# PIRT1280A1-12-breakout.net
KiCad netlist of a schematic drawn in EAGLE
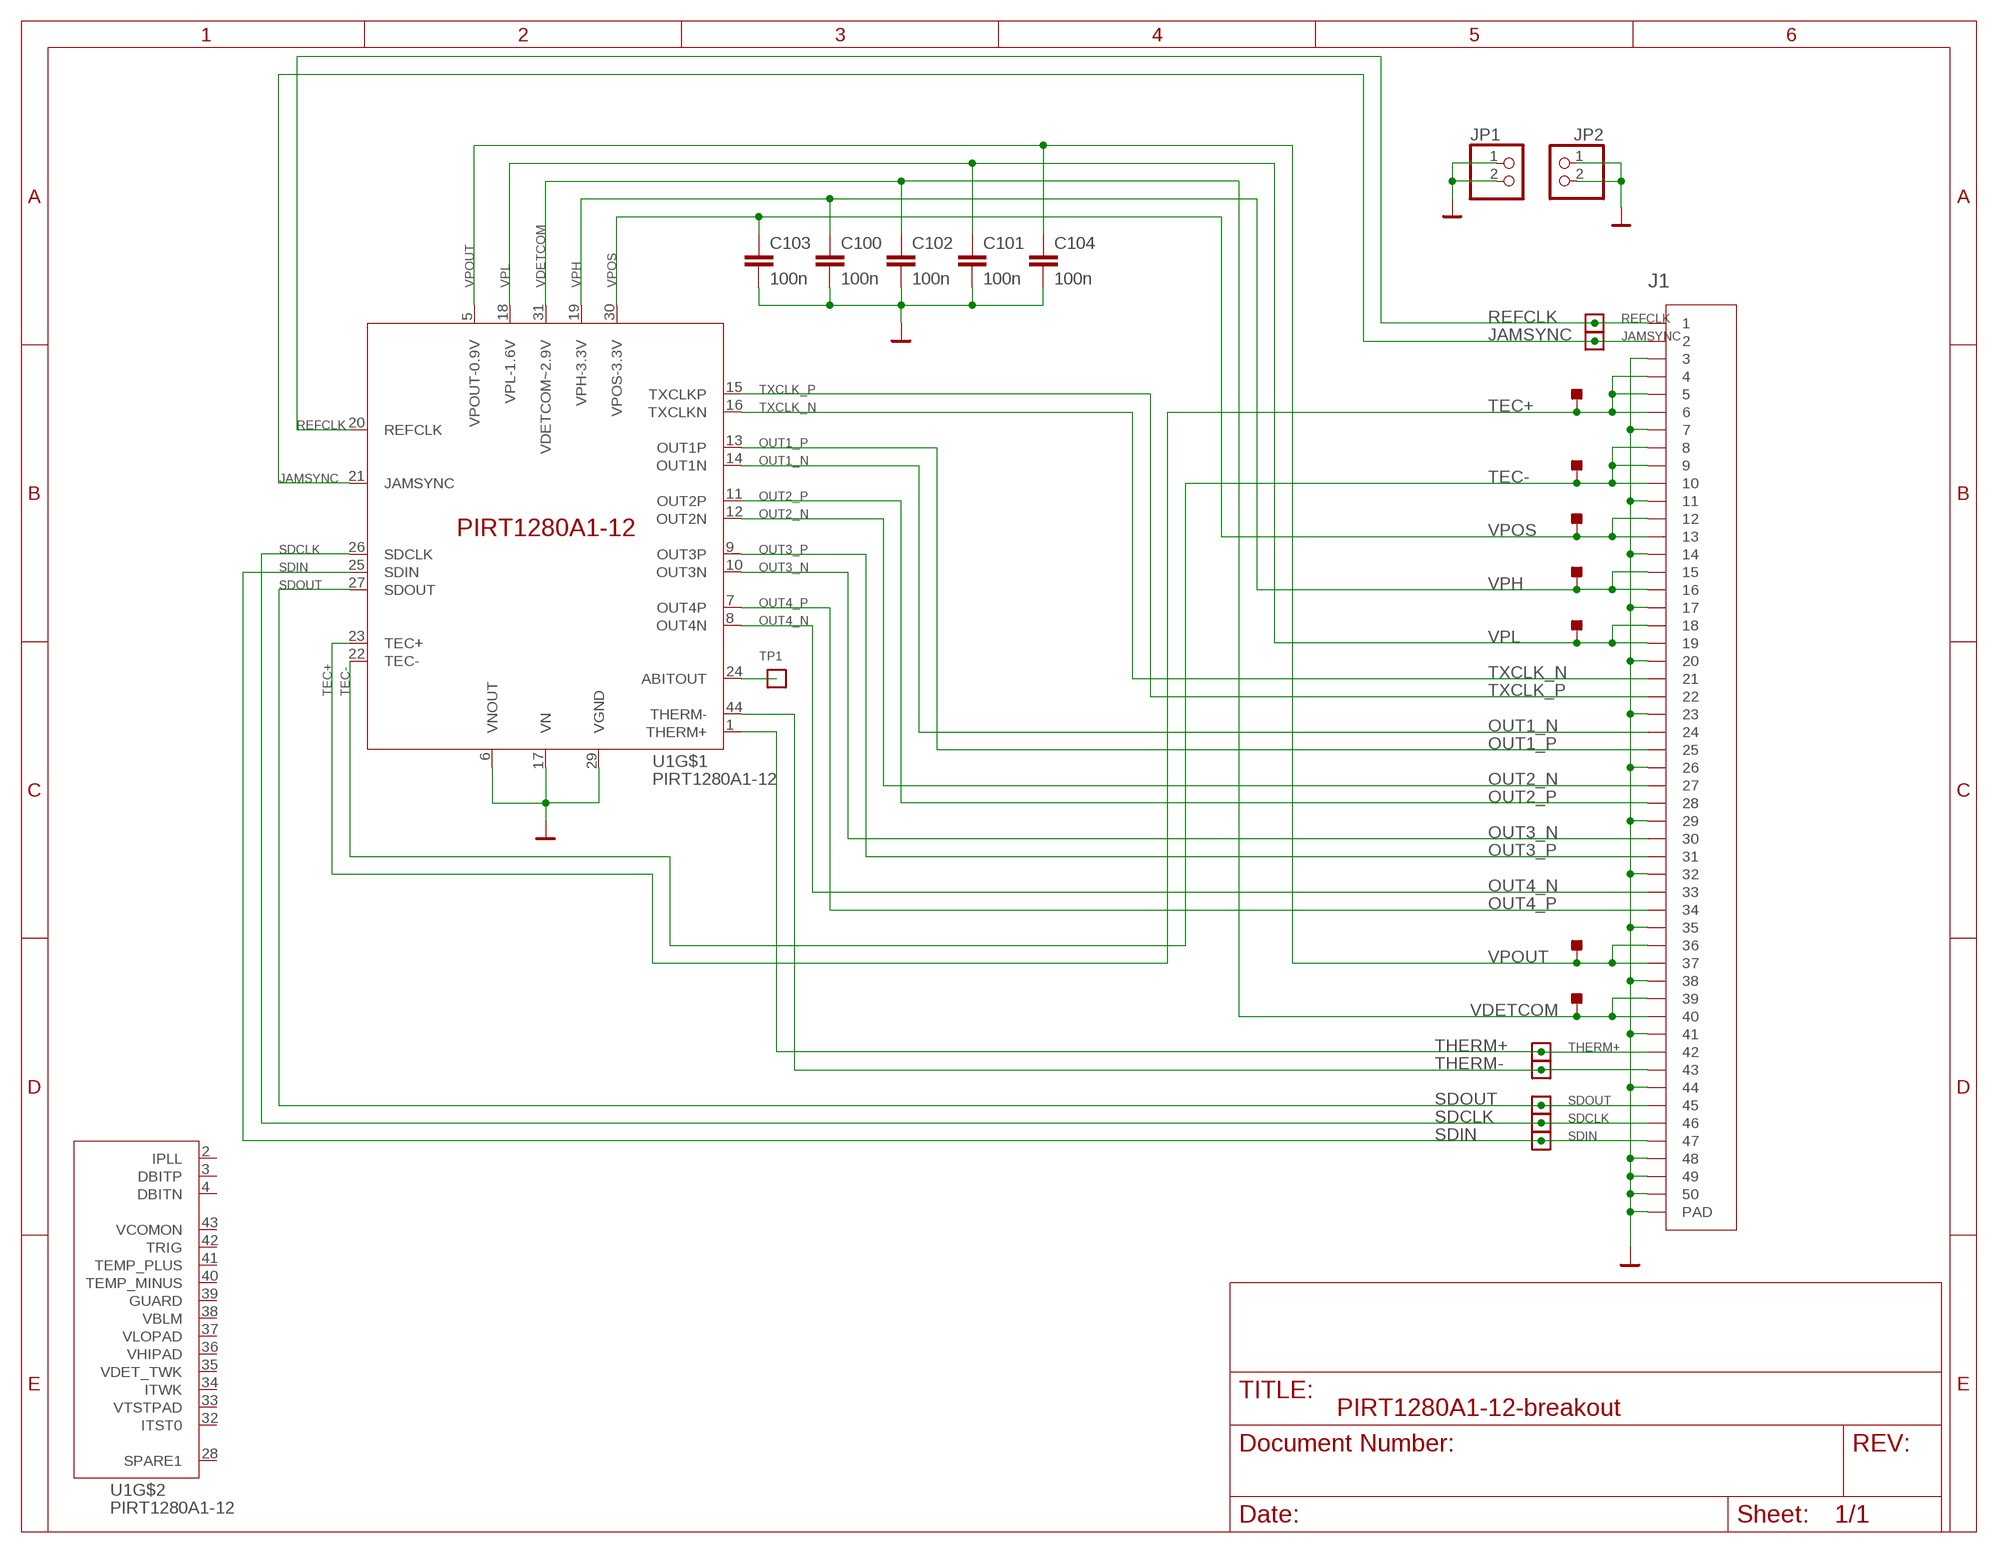
[diagram p0: schematic, sheet 1]

(export (version "E")
  (design (tool "Eeschema 10.0.6"))
  (components
    (comp (ref "C100")
      (value "100n")
      (footprint "eagle-import:.0805-A")
      (libsource (lib "eagle-import") (part "C-EU0805-A"))
    )
    (comp (ref "C101")
      (value "100n")
      (footprint "eagle-import:.0805-A")
      (libsource (lib "eagle-import") (part "C-EU0805-A"))
    )
    (comp (ref "C102")
      (value "100n")
      (footprint "eagle-import:.0805-A")
      (libsource (lib "eagle-import") (part "C-EU0805-A"))
    )
    (comp (ref "C103")
      (value "100n")
      (footprint "eagle-import:.0805-A")
      (libsource (lib "eagle-import") (part "C-EU0805-A"))
    )
    (comp (ref "C104")
      (value "100n")
      (footprint "eagle-import:.0805-A")
      (libsource (lib "eagle-import") (part "C-EU0805-A"))
    )
    (comp (ref "J1")
      (value "5-1734592-0")
      (footprint "eagle-import:TE_5-1734592-0")
      (libsource (lib "eagle-import") (part "5-1734592-0"))
    )
    (comp (ref "JAMSYNC")
      (value "TEST-POINT-LARGE-SQUARE")
      (footprint "eagle-import:1X01")
      (libsource (lib "eagle-import") (part "TEST-POINT-LARGE-SQUARE"))
    )
    (comp (ref "JP1")
      (value "PINHD-1X2")
      (footprint "eagle-import:1X02")
      (libsource (lib "eagle-import") (part "PINHD-1X2"))
    )
    (comp (ref "JP2")
      (value "PINHD-1X2")
      (footprint "eagle-import:1X02")
      (libsource (lib "eagle-import") (part "PINHD-1X2"))
    )
    (comp (ref "REFCLK")
      (value "TEST-POINT-LARGE-SQUARE")
      (footprint "eagle-import:1X01")
      (libsource (lib "eagle-import") (part "TEST-POINT-LARGE-SQUARE"))
    )
    (comp (ref "SDCLK")
      (value "TEST-POINT-LARGE-SQUARE")
      (footprint "eagle-import:1X01")
      (libsource (lib "eagle-import") (part "TEST-POINT-LARGE-SQUARE"))
    )
    (comp (ref "SDIN")
      (value "TEST-POINT-LARGE-SQUARE")
      (footprint "eagle-import:1X01")
      (libsource (lib "eagle-import") (part "TEST-POINT-LARGE-SQUARE"))
    )
    (comp (ref "SDOUT")
      (value "TEST-POINT-LARGE-SQUARE")
      (footprint "eagle-import:1X01")
      (libsource (lib "eagle-import") (part "TEST-POINT-LARGE-SQUARE"))
    )
    (comp (ref "TEC+")
      (value "TEST-POINT_SMD-SMD-10SN")
      (footprint "eagle-import:TESTPOINT_SMD-10SN")
      (libsource (lib "eagle-import") (part "TEST-POINT_SMD-SMD-10SN"))
    )
    (comp (ref "TEC-")
      (value "TEST-POINT_SMD-SMD-10SN")
      (footprint "eagle-import:TESTPOINT_SMD-10SN")
      (libsource (lib "eagle-import") (part "TEST-POINT_SMD-SMD-10SN"))
    )
    (comp (ref "THERM+")
      (value "TEST-POINT-LARGE-SQUARE")
      (footprint "eagle-import:1X01")
      (libsource (lib "eagle-import") (part "TEST-POINT-LARGE-SQUARE"))
    )
    (comp (ref "THERM-")
      (value "TEST-POINT-LARGE-SQUARE")
      (footprint "eagle-import:1X01")
      (libsource (lib "eagle-import") (part "TEST-POINT-LARGE-SQUARE"))
    )
    (comp (ref "TP1")
      (value "TEST-POINT-LARGE-SQUARE")
      (footprint "eagle-import:1X01")
      (libsource (lib "eagle-import") (part "TEST-POINT-LARGE-SQUARE"))
    )
    (comp (ref "U1")
      (value "PIRT1280A1-12")
      (footprint "eagle-import:PIRT1280A1-12")
      (libsource (lib "eagle-import") (part "PIRT1280A1-12"))
    )
    (comp (ref "VDETCOM")
      (value "TEST-POINT_SMD-SMD-10SN")
      (footprint "eagle-import:TESTPOINT_SMD-10SN")
      (libsource (lib "eagle-import") (part "TEST-POINT_SMD-SMD-10SN"))
    )
    (comp (ref "VPH")
      (value "TEST-POINT_SMD-SMD-10SN")
      (footprint "eagle-import:TESTPOINT_SMD-10SN")
      (libsource (lib "eagle-import") (part "TEST-POINT_SMD-SMD-10SN"))
    )
    (comp (ref "VPL")
      (value "TEST-POINT_SMD-SMD-10SN")
      (footprint "eagle-import:TESTPOINT_SMD-10SN")
      (libsource (lib "eagle-import") (part "TEST-POINT_SMD-SMD-10SN"))
    )
    (comp (ref "VPOS")
      (value "TEST-POINT_SMD-SMD-10SN")
      (footprint "eagle-import:TESTPOINT_SMD-10SN")
      (libsource (lib "eagle-import") (part "TEST-POINT_SMD-SMD-10SN"))
    )
    (comp (ref "VPOUT")
      (value "TEST-POINT_SMD-SMD-10SN")
      (footprint "eagle-import:TESTPOINT_SMD-10SN")
      (libsource (lib "eagle-import") (part "TEST-POINT_SMD-SMD-10SN"))
    )
  )
  (nets
    (net (code "1") (name "/JAMSYNC") (class "Default")
      (node (ref "J1") (pin "2") (pinfunction "2_2") (pintype "passive"))
      (node (ref "JAMSYNC") (pin "1") (pinfunction "1_1") (pintype "passive"))
      (node (ref "U1") (pin "21") (pinfunction "JAMSYNC_21") (pintype "input"))
    )
    (net (code "2") (name "/OUT1_N") (class "Default")
      (node (ref "J1") (pin "24") (pinfunction "24_24") (pintype "passive"))
      (node (ref "U1") (pin "14") (pinfunction "OUT1N_14") (pintype "output"))
    )
    (net (code "3") (name "/OUT1_P") (class "Default")
      (node (ref "J1") (pin "25") (pinfunction "25_25") (pintype "passive"))
      (node (ref "U1") (pin "13") (pinfunction "OUT1P_13") (pintype "output"))
    )
    (net (code "4") (name "/OUT2_N") (class "Default")
      (node (ref "J1") (pin "27") (pinfunction "27_27") (pintype "passive"))
      (node (ref "U1") (pin "12") (pinfunction "OUT2N_12") (pintype "output"))
    )
    (net (code "5") (name "/OUT2_P") (class "Default")
      (node (ref "J1") (pin "28") (pinfunction "28_28") (pintype "passive"))
      (node (ref "U1") (pin "11") (pinfunction "OUT2P_11") (pintype "output"))
    )
    (net (code "6") (name "/OUT3_N") (class "Default")
      (node (ref "J1") (pin "30") (pinfunction "30_30") (pintype "passive"))
      (node (ref "U1") (pin "10") (pinfunction "OUT3N_10") (pintype "output"))
    )
    (net (code "7") (name "/OUT3_P") (class "Default")
      (node (ref "J1") (pin "31") (pinfunction "31_31") (pintype "passive"))
      (node (ref "U1") (pin "9") (pinfunction "OUT3P_9") (pintype "output"))
    )
    (net (code "8") (name "/OUT4_N") (class "Default")
      (node (ref "J1") (pin "33") (pinfunction "33_33") (pintype "passive"))
      (node (ref "U1") (pin "8") (pinfunction "OUT4N_8") (pintype "output"))
    )
    (net (code "9") (name "/OUT4_P") (class "Default")
      (node (ref "J1") (pin "34") (pinfunction "34_34") (pintype "passive"))
      (node (ref "U1") (pin "7") (pinfunction "OUT4P_7") (pintype "output"))
    )
    (net (code "10") (name "/REFCLK") (class "Default")
      (node (ref "J1") (pin "1") (pinfunction "1_1") (pintype "passive"))
      (node (ref "REFCLK") (pin "1") (pinfunction "1_1") (pintype "passive"))
      (node (ref "U1") (pin "20") (pinfunction "REFCLK_20") (pintype "input"))
    )
    (net (code "11") (name "/SDCLK") (class "Default")
      (node (ref "J1") (pin "46") (pinfunction "46_46") (pintype "passive"))
      (node (ref "SDCLK") (pin "1") (pinfunction "1_1") (pintype "passive"))
      (node (ref "U1") (pin "26") (pinfunction "SDCLK_26") (pintype "input"))
    )
    (net (code "12") (name "/SDIN") (class "Default")
      (node (ref "J1") (pin "47") (pinfunction "47_47") (pintype "passive"))
      (node (ref "SDIN") (pin "1") (pinfunction "1_1") (pintype "passive"))
      (node (ref "U1") (pin "25") (pinfunction "SDIN_25") (pintype "input"))
    )
    (net (code "13") (name "/SDOUT") (class "Default")
      (node (ref "J1") (pin "45") (pinfunction "45_45") (pintype "passive"))
      (node (ref "SDOUT") (pin "1") (pinfunction "1_1") (pintype "passive"))
      (node (ref "U1") (pin "27") (pinfunction "SDOUT_27") (pintype "output"))
    )
    (net (code "14") (name "/TEC+") (class "Default")
      (node (ref "J1") (pin "4") (pinfunction "4_4") (pintype "passive"))
      (node (ref "J1") (pin "5") (pinfunction "5_5") (pintype "passive"))
      (node (ref "J1") (pin "6") (pinfunction "6_6") (pintype "passive"))
      (node (ref "TEC+") (pin "TP") (pinfunction "TP_TP") (pintype "passive"))
      (node (ref "U1") (pin "23") (pinfunction "TEC+_23") (pintype "passive"))
    )
    (net (code "15") (name "/TEC-") (class "Default")
      (node (ref "J1") (pin "10") (pinfunction "10_10") (pintype "passive"))
      (node (ref "J1") (pin "8") (pinfunction "8_8") (pintype "passive"))
      (node (ref "J1") (pin "9") (pinfunction "9_9") (pintype "passive"))
      (node (ref "TEC-") (pin "TP") (pinfunction "TP_TP") (pintype "passive"))
      (node (ref "U1") (pin "22") (pinfunction "TEC-_22") (pintype "passive"))
    )
    (net (code "16") (name "/THERM+") (class "Default")
      (node (ref "J1") (pin "42") (pinfunction "42_42") (pintype "passive"))
      (node (ref "THERM+") (pin "1") (pinfunction "1_1") (pintype "passive"))
      (node (ref "U1") (pin "1") (pinfunction "THERM+_1") (pintype "passive"))
    )
    (net (code "17") (name "/THERM-") (class "Default")
      (node (ref "J1") (pin "43") (pinfunction "43_43") (pintype "passive"))
      (node (ref "THERM-") (pin "1") (pinfunction "1_1") (pintype "passive"))
      (node (ref "U1") (pin "44") (pinfunction "THERM-_44") (pintype "passive"))
    )
    (net (code "18") (name "/TXCLK_N") (class "Default")
      (node (ref "J1") (pin "21") (pinfunction "21_21") (pintype "passive"))
      (node (ref "U1") (pin "16") (pinfunction "TXCLKN_16") (pintype "output"))
    )
    (net (code "19") (name "/TXCLK_P") (class "Default")
      (node (ref "J1") (pin "22") (pinfunction "22_22") (pintype "passive"))
      (node (ref "U1") (pin "15") (pinfunction "TXCLKP_15") (pintype "output"))
    )
    (net (code "20") (name "/VDETCOM") (class "Default")
      (node (ref "C102") (pin "1") (pinfunction "1_1") (pintype "passive"))
      (node (ref "J1") (pin "39") (pinfunction "39_39") (pintype "passive"))
      (node (ref "J1") (pin "40") (pinfunction "40_40") (pintype "passive"))
      (node (ref "U1") (pin "31") (pinfunction "VDETCOM~{2.9V}_31") (pintype "power_in"))
      (node (ref "VDETCOM") (pin "TP") (pinfunction "TP_TP") (pintype "passive"))
    )
    (net (code "21") (name "/VPH") (class "Default")
      (node (ref "C100") (pin "1") (pinfunction "1_1") (pintype "passive"))
      (node (ref "J1") (pin "15") (pinfunction "15_15") (pintype "passive"))
      (node (ref "J1") (pin "16") (pinfunction "16_16") (pintype "passive"))
      (node (ref "U1") (pin "19") (pinfunction "VPH-3.3V_19") (pintype "power_in"))
      (node (ref "VPH") (pin "TP") (pinfunction "TP_TP") (pintype "passive"))
    )
    (net (code "22") (name "/VPL") (class "Default")
      (node (ref "C101") (pin "1") (pinfunction "1_1") (pintype "passive"))
      (node (ref "J1") (pin "18") (pinfunction "18_18") (pintype "passive"))
      (node (ref "J1") (pin "19") (pinfunction "19_19") (pintype "passive"))
      (node (ref "U1") (pin "18") (pinfunction "VPL-1.6V_18") (pintype "power_in"))
      (node (ref "VPL") (pin "TP") (pinfunction "TP_TP") (pintype "passive"))
    )
    (net (code "23") (name "/VPOS") (class "Default")
      (node (ref "C103") (pin "1") (pinfunction "1_1") (pintype "passive"))
      (node (ref "J1") (pin "12") (pinfunction "12_12") (pintype "passive"))
      (node (ref "J1") (pin "13") (pinfunction "13_13") (pintype "passive"))
      (node (ref "U1") (pin "30") (pinfunction "VPOS-3.3V_30") (pintype "power_in"))
      (node (ref "VPOS") (pin "TP") (pinfunction "TP_TP") (pintype "passive"))
    )
    (net (code "24") (name "/VPOUT") (class "Default")
      (node (ref "C104") (pin "1") (pinfunction "1_1") (pintype "passive"))
      (node (ref "J1") (pin "36") (pinfunction "36_36") (pintype "passive"))
      (node (ref "J1") (pin "37") (pinfunction "37_37") (pintype "passive"))
      (node (ref "U1") (pin "5") (pinfunction "VPOUT-0.9V_5") (pintype "power_in"))
      (node (ref "VPOUT") (pin "TP") (pinfunction "TP_TP") (pintype "passive"))
    )
    (net (code "25") (name "GND") (class "Default")
      (node (ref "C100") (pin "2") (pinfunction "2_2") (pintype "passive"))
      (node (ref "C101") (pin "2") (pinfunction "2_2") (pintype "passive"))
      (node (ref "C102") (pin "2") (pinfunction "2_2") (pintype "passive"))
      (node (ref "C103") (pin "2") (pinfunction "2_2") (pintype "passive"))
      (node (ref "C104") (pin "2") (pinfunction "2_2") (pintype "passive"))
      (node (ref "J1") (pin "11") (pinfunction "11_11") (pintype "passive"))
      (node (ref "J1") (pin "14") (pinfunction "14_14") (pintype "passive"))
      (node (ref "J1") (pin "17") (pinfunction "17_17") (pintype "passive"))
      (node (ref "J1") (pin "20") (pinfunction "20_20") (pintype "passive"))
      (node (ref "J1") (pin "23") (pinfunction "23_23") (pintype "passive"))
      (node (ref "J1") (pin "26") (pinfunction "26_26") (pintype "passive"))
      (node (ref "J1") (pin "29") (pinfunction "29_29") (pintype "passive"))
      (node (ref "J1") (pin "3") (pinfunction "3_3") (pintype "passive"))
      (node (ref "J1") (pin "32") (pinfunction "32_32") (pintype "passive"))
      (node (ref "J1") (pin "35") (pinfunction "35_35") (pintype "passive"))
      (node (ref "J1") (pin "38") (pinfunction "38_38") (pintype "passive"))
      (node (ref "J1") (pin "41") (pinfunction "41_41") (pintype "passive"))
      (node (ref "J1") (pin "44") (pinfunction "44_44") (pintype "passive"))
      (node (ref "J1") (pin "48") (pinfunction "48_48") (pintype "passive"))
      (node (ref "J1") (pin "49") (pinfunction "49_49") (pintype "passive"))
      (node (ref "J1") (pin "50") (pinfunction "50_50") (pintype "passive"))
      (node (ref "J1") (pin "7") (pinfunction "7_7") (pintype "passive"))
      (node (ref "J1") (pin "S1") (pinfunction "PAD_S1") (pintype "bidirectional"))
      (node (ref "J1") (pin "S2") (pinfunction "PAD_S2") (pintype "bidirectional"))
      (node (ref "JP1") (pin "1") (pinfunction "1_1") (pintype "passive"))
      (node (ref "JP1") (pin "2") (pinfunction "2_2") (pintype "passive"))
      (node (ref "JP2") (pin "1") (pinfunction "1_1") (pintype "passive"))
      (node (ref "JP2") (pin "2") (pinfunction "2_2") (pintype "passive"))
      (node (ref "U1") (pin "17") (pinfunction "VN_17") (pintype "power_in"))
      (node (ref "U1") (pin "29") (pinfunction "VGND_29") (pintype "power_in"))
      (node (ref "U1") (pin "6") (pinfunction "VNOUT_6") (pintype "power_in"))
    )
    (net (code "26") (name "Net-(U1A-ABITOUT)") (class "Default")
      (node (ref "TP1") (pin "1") (pinfunction "1_1") (pintype "passive"))
      (node (ref "U1") (pin "24") (pinfunction "ABITOUT_24") (pintype "output"))
    )
    (net (code "27") (name "unconnected-(U1B-DBITN-Pad4)") (class "Default")
      (node (ref "U1") (pin "4") (pinfunction "DBITN_4") (pintype "no_connect"))
    )
    (net (code "28") (name "unconnected-(U1B-DBITP-Pad3)") (class "Default")
      (node (ref "U1") (pin "3") (pinfunction "DBITP_3") (pintype "no_connect"))
    )
    (net (code "29") (name "unconnected-(U1B-GUARD-Pad39)") (class "Default")
      (node (ref "U1") (pin "39") (pinfunction "GUARD_39") (pintype "no_connect"))
    )
    (net (code "30") (name "unconnected-(U1B-IPLL-Pad2)") (class "Default")
      (node (ref "U1") (pin "2") (pinfunction "IPLL_2") (pintype "no_connect"))
    )
    (net (code "31") (name "unconnected-(U1B-ITST0-Pad32)") (class "Default")
      (node (ref "U1") (pin "32") (pinfunction "ITST0_32") (pintype "no_connect"))
    )
    (net (code "32") (name "unconnected-(U1B-ITWK-Pad34)") (class "Default")
      (node (ref "U1") (pin "34") (pinfunction "ITWK_34") (pintype "no_connect"))
    )
    (net (code "33") (name "unconnected-(U1B-SPARE1-Pad28)") (class "Default")
      (node (ref "U1") (pin "28") (pinfunction "SPARE1_28") (pintype "no_connect"))
    )
    (net (code "34") (name "unconnected-(U1B-TEMP_MINUS-Pad40)") (class "Default")
      (node (ref "U1") (pin "40") (pinfunction "TEMP_MINUS_40") (pintype "no_connect"))
    )
    (net (code "35") (name "unconnected-(U1B-TEMP_PLUS-Pad41)") (class "Default")
      (node (ref "U1") (pin "41") (pinfunction "TEMP_PLUS_41") (pintype "no_connect"))
    )
    (net (code "36") (name "unconnected-(U1B-TRIG-Pad42)") (class "Default")
      (node (ref "U1") (pin "42") (pinfunction "TRIG_42") (pintype "no_connect"))
    )
    (net (code "37") (name "unconnected-(U1B-VBLM-Pad38)") (class "Default")
      (node (ref "U1") (pin "38") (pinfunction "VBLM_38") (pintype "no_connect"))
    )
    (net (code "38") (name "unconnected-(U1B-VCOMON-Pad43)") (class "Default")
      (node (ref "U1") (pin "43") (pinfunction "VCOMON_43") (pintype "no_connect"))
    )
    (net (code "39") (name "unconnected-(U1B-VDET_TWK-Pad35)") (class "Default")
      (node (ref "U1") (pin "35") (pinfunction "VDET_TWK_35") (pintype "no_connect"))
    )
    (net (code "40") (name "unconnected-(U1B-VHIPAD-Pad36)") (class "Default")
      (node (ref "U1") (pin "36") (pinfunction "VHIPAD_36") (pintype "no_connect"))
    )
    (net (code "41") (name "unconnected-(U1B-VLOPAD-Pad37)") (class "Default")
      (node (ref "U1") (pin "37") (pinfunction "VLOPAD_37") (pintype "no_connect"))
    )
    (net (code "42") (name "unconnected-(U1B-VTSTPAD-Pad33)") (class "Default")
      (node (ref "U1") (pin "33") (pinfunction "VTSTPAD_33") (pintype "no_connect"))
    )
  )
)
